# Power_Link.net
KiCad netlist of a schematic drawn in EAGLE
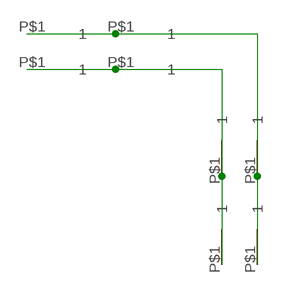
[diagram p0: schematic, sheet 1]

(export (version "E")
  (design (tool "Eeschema 10.0.6"))
  (components
    (comp (ref "PIN1")
      (value "0945-0-15-20-09-14-11-0")
      (footprint "eagle-import:MILL_MAX_0945_SMD")
      (fields (field (name "MANUFACTURER") "Mill-Max"))
      (libsource (lib "eagle-import") (part "0945-0-15-20-09-14-11-0"))
    )
    (comp (ref "PIN2")
      (value "0945-0-15-20-09-14-11-0")
      (footprint "eagle-import:MILL_MAX_0945_SMD")
      (fields (field (name "MANUFACTURER") "Mill-Max"))
      (libsource (lib "eagle-import") (part "0945-0-15-20-09-14-11-0"))
    )
    (comp (ref "PIN3")
      (value "0945-0-15-20-09-14-11-0")
      (footprint "eagle-import:MILL_MAX_0945_SMD")
      (fields (field (name "MANUFACTURER") "Mill-Max"))
      (libsource (lib "eagle-import") (part "0945-0-15-20-09-14-11-0"))
    )
    (comp (ref "PIN4")
      (value "0945-0-15-20-09-14-11-0")
      (footprint "eagle-import:MILL_MAX_0945_SMD")
      (fields (field (name "MANUFACTURER") "Mill-Max"))
      (libsource (lib "eagle-import") (part "0945-0-15-20-09-14-11-0"))
    )
    (comp (ref "PIN5")
      (value "0945-0-15-20-09-14-11-0")
      (footprint "eagle-import:MILL_MAX_0945_SMD")
      (fields (field (name "MANUFACTURER") "Mill-Max"))
      (libsource (lib "eagle-import") (part "0945-0-15-20-09-14-11-0"))
    )
    (comp (ref "PIN6")
      (value "0945-0-15-20-09-14-11-0")
      (footprint "eagle-import:MILL_MAX_0945_SMD")
      (fields (field (name "MANUFACTURER") "Mill-Max"))
      (libsource (lib "eagle-import") (part "0945-0-15-20-09-14-11-0"))
    )
    (comp (ref "PIN7")
      (value "0945-0-15-20-09-14-11-0")
      (footprint "eagle-import:MILL_MAX_0945_SMD")
      (fields (field (name "MANUFACTURER") "Mill-Max"))
      (libsource (lib "eagle-import") (part "0945-0-15-20-09-14-11-0"))
    )
    (comp (ref "PIN8")
      (value "0945-0-15-20-09-14-11-0")
      (footprint "eagle-import:MILL_MAX_0945_SMD")
      (fields (field (name "MANUFACTURER") "Mill-Max"))
      (libsource (lib "eagle-import") (part "0945-0-15-20-09-14-11-0"))
    )
  )
  (nets
    (net (code "1") (name "Net-(PIN1-1)") (class "Default")
      (node (ref "PIN1") (pin "P$1") (pinfunction "1_P$1") (pintype "bidirectional"))
      (node (ref "PIN3") (pin "P$1") (pinfunction "1_P$1") (pintype "bidirectional"))
      (node (ref "PIN5") (pin "P$1") (pinfunction "1_P$1") (pintype "bidirectional"))
      (node (ref "PIN7") (pin "P$1") (pinfunction "1_P$1") (pintype "bidirectional"))
    )
    (net (code "2") (name "Net-(PIN2-1)") (class "Default")
      (node (ref "PIN2") (pin "P$1") (pinfunction "1_P$1") (pintype "bidirectional"))
      (node (ref "PIN4") (pin "P$1") (pinfunction "1_P$1") (pintype "bidirectional"))
      (node (ref "PIN6") (pin "P$1") (pinfunction "1_P$1") (pintype "bidirectional"))
      (node (ref "PIN8") (pin "P$1") (pinfunction "1_P$1") (pintype "bidirectional"))
    )
  )
)
